# mainPower.net
KiCad netlist of a schematic drawn in Altium Designer
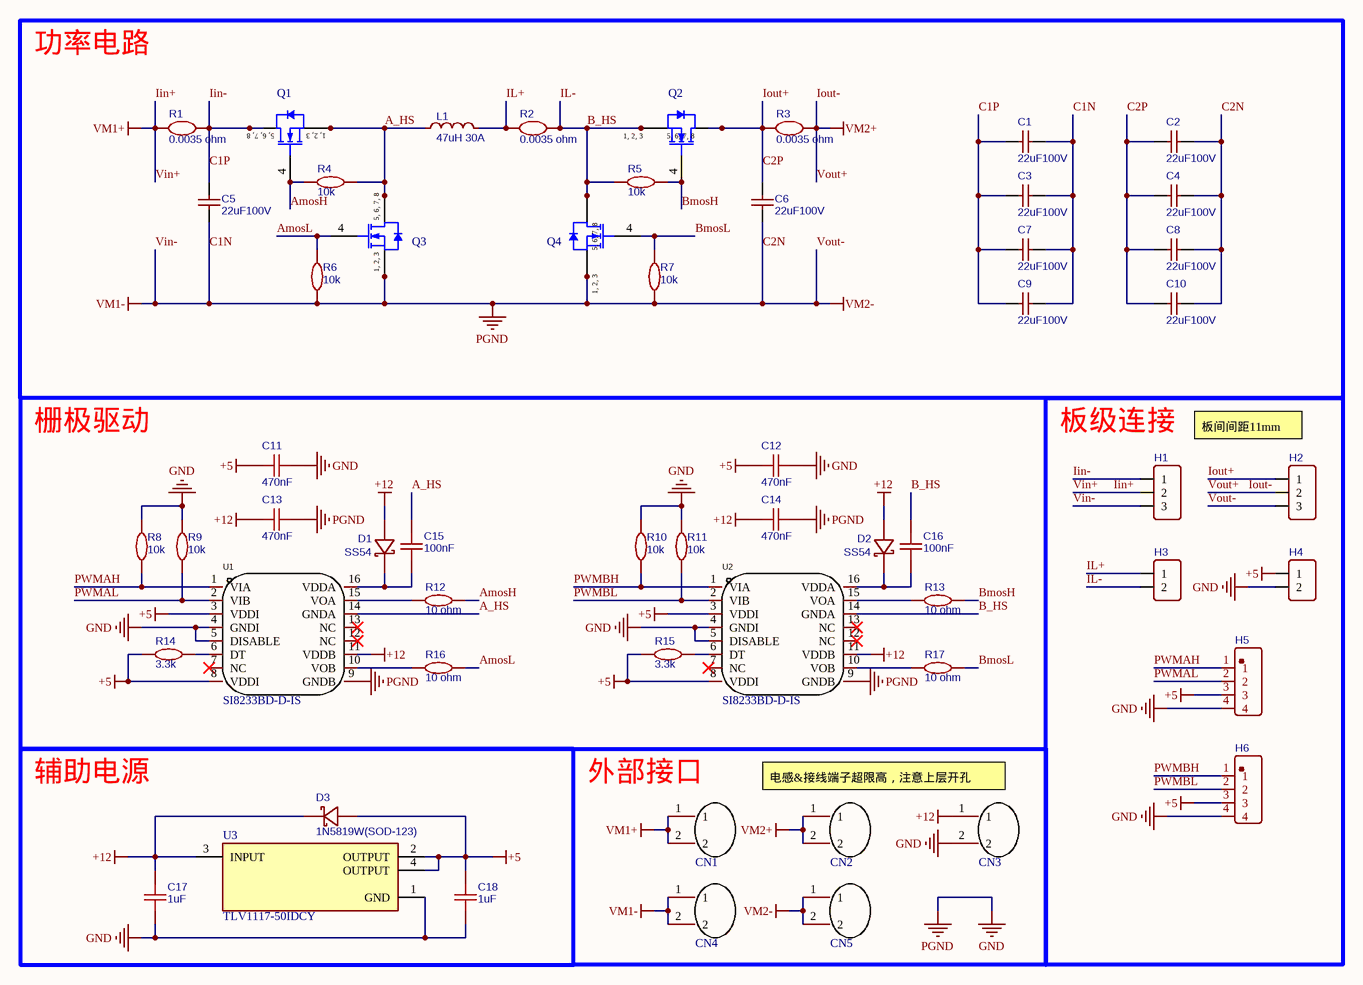
[diagram p0: mainPower.SchDoc]

(export (version "E")
  (design (tool "Eeschema 10.0.6"))
  (components
    (comp (ref "C1")
      (value "22uF100V")
      (footprint "C1206")
      (fields
        (field (name "BOM_MANUFACTURER PART") "1206B102K202NT")
        (field (name "BOM_SUPPLIER PART") "C9196")
      )
      (libsource (lib "RC_schlib") (part "C1206"))
    )
    (comp (ref "C2")
      (value "22uF100V")
      (footprint "C1206")
      (fields
        (field (name "BOM_MANUFACTURER PART") "1206B102K202NT")
        (field (name "BOM_SUPPLIER PART") "C9196")
      )
      (libsource (lib "RC_schlib") (part "C1206"))
    )
    (comp (ref "C3")
      (value "22uF100V")
      (footprint "C1206")
      (fields
        (field (name "BOM_MANUFACTURER PART") "1206B102K202NT")
        (field (name "BOM_SUPPLIER PART") "C9196")
      )
      (libsource (lib "RC_schlib") (part "C1206"))
    )
    (comp (ref "C4")
      (value "22uF100V")
      (footprint "C1206")
      (fields
        (field (name "BOM_MANUFACTURER PART") "1206B102K202NT")
        (field (name "BOM_SUPPLIER PART") "C9196")
      )
      (libsource (lib "RC_schlib") (part "C1206"))
    )
    (comp (ref "C5")
      (value "22uF100V")
      (footprint "C1206")
      (fields
        (field (name "BOM_MANUFACTURER PART") "1206B102K202NT")
        (field (name "BOM_SUPPLIER PART") "C9196")
      )
      (libsource (lib "RC_schlib") (part "C1206"))
    )
    (comp (ref "C6")
      (value "22uF100V")
      (footprint "C1206")
      (fields
        (field (name "BOM_MANUFACTURER PART") "1206B102K202NT")
        (field (name "BOM_SUPPLIER PART") "C9196")
      )
      (libsource (lib "RC_schlib") (part "C1206"))
    )
    (comp (ref "C7")
      (value "22uF100V")
      (footprint "C1206")
      (fields
        (field (name "BOM_MANUFACTURER PART") "1206B102K202NT")
        (field (name "BOM_SUPPLIER PART") "C9196")
      )
      (libsource (lib "RC_schlib") (part "C1206"))
    )
    (comp (ref "C8")
      (value "22uF100V")
      (footprint "C1206")
      (fields
        (field (name "BOM_MANUFACTURER PART") "1206B102K202NT")
        (field (name "BOM_SUPPLIER PART") "C9196")
      )
      (libsource (lib "RC_schlib") (part "C1206"))
    )
    (comp (ref "C9")
      (value "22uF100V")
      (footprint "C1206")
      (fields
        (field (name "BOM_MANUFACTURER PART") "1206B102K202NT")
        (field (name "BOM_SUPPLIER PART") "C9196")
      )
      (libsource (lib "RC_schlib") (part "C1206"))
    )
    (comp (ref "C10")
      (value "22uF100V")
      (footprint "C1206")
      (fields
        (field (name "BOM_MANUFACTURER PART") "1206B102K202NT")
        (field (name "BOM_SUPPLIER PART") "C9196")
      )
      (libsource (lib "RC_schlib") (part "C1206"))
    )
    (comp (ref "C11")
      (value "470nF")
      (footprint "C0603")
      (fields
        (field (name "BOM_MANUFACTURER PART") "CC0603KRX7R9BB104")
        (field (name "BOM_SUPPLIER PART") "C14663")
      )
      (libsource (lib "RC_schlib") (part "C0603"))
    )
    (comp (ref "C12")
      (value "470nF")
      (footprint "C0603")
      (fields
        (field (name "BOM_MANUFACTURER PART") "CC0603KRX7R9BB104")
        (field (name "BOM_SUPPLIER PART") "C14663")
      )
      (libsource (lib "RC_schlib") (part "C0603"))
    )
    (comp (ref "C13")
      (value "470nF")
      (footprint "C0603")
      (fields
        (field (name "BOM_MANUFACTURER PART") "CC0603KRX7R9BB104")
        (field (name "BOM_SUPPLIER PART") "C14663")
      )
      (libsource (lib "RC_schlib") (part "C0603"))
    )
    (comp (ref "C14")
      (value "470nF")
      (footprint "C0603")
      (fields
        (field (name "BOM_MANUFACTURER PART") "CC0603KRX7R9BB104")
        (field (name "BOM_SUPPLIER PART") "C14663")
      )
      (libsource (lib "RC_schlib") (part "C0603"))
    )
    (comp (ref "C15")
      (value "100nF")
      (footprint "C0603")
      (fields
        (field (name "BOM_MANUFACTURER PART") "CC0603KRX7R9BB104")
        (field (name "BOM_SUPPLIER PART") "C14663")
      )
      (libsource (lib "RC_schlib") (part "C0603"))
    )
    (comp (ref "C16")
      (value "100nF")
      (footprint "C0603")
      (fields
        (field (name "BOM_MANUFACTURER PART") "CC0603KRX7R9BB104")
        (field (name "BOM_SUPPLIER PART") "C14663")
      )
      (libsource (lib "RC_schlib") (part "C0603"))
    )
    (comp (ref "C17")
      (value "1uF")
      (footprint "C0603")
      (fields
        (field (name "BOM_MANUFACTURER PART") "CC0603KRX7R9BB104")
        (field (name "BOM_SUPPLIER PART") "C14663")
      )
      (libsource (lib "RC_schlib") (part "C0603"))
    )
    (comp (ref "C18")
      (value "1uF")
      (footprint "C0603")
      (fields
        (field (name "BOM_MANUFACTURER PART") "CC0603KRX7R9BB104")
        (field (name "BOM_SUPPLIER PART") "C14663")
      )
      (libsource (lib "RC_schlib") (part "C0603"))
    )
    (comp (ref "CN1")
      (value "1729128")
      (footprint "CONN-TH_2P-P5.08")
      (description "间距:5.08mm;排数:1;每排PIN数:2;安装方式:直针;额定电流:13.5A;额定电压:400V;工作温度范围:-;颜色:绿色;")
      (fields (field (name "MANUFACTURER") "Phoenix Contact(菲尼克斯)"))
      (libsource (lib "MKDSN") (part "MKDSN5.08-2P"))
    )
    (comp (ref "CN2")
      (value "1729128")
      (footprint "CONN-TH_2P-P5.08")
      (description "间距:5.08mm;排数:1;每排PIN数:2;安装方式:直针;额定电流:13.5A;额定电压:400V;工作温度范围:-;颜色:绿色;")
      (fields (field (name "MANUFACTURER") "Phoenix Contact(菲尼克斯)"))
      (libsource (lib "MKDSN") (part "MKDSN5.08-2P"))
    )
    (comp (ref "CN3")
      (value "1729128")
      (footprint "CONN-TH_2P-P5.08")
      (description "间距:5.08mm;排数:1;每排PIN数:2;安装方式:直针;额定电流:13.5A;额定电压:400V;工作温度范围:-;颜色:绿色;")
      (fields (field (name "MANUFACTURER") "Phoenix Contact(菲尼克斯)"))
      (libsource (lib "MKDSN") (part "MKDSN5.08-2P"))
    )
    (comp (ref "CN4")
      (value "1729128")
      (footprint "CONN-TH_2P-P5.08")
      (description "间距:5.08mm;排数:1;每排PIN数:2;安装方式:直针;额定电流:13.5A;额定电压:400V;工作温度范围:-;颜色:绿色;")
      (fields (field (name "MANUFACTURER") "Phoenix Contact(菲尼克斯)"))
      (libsource (lib "MKDSN") (part "MKDSN5.08-2P"))
    )
    (comp (ref "CN5")
      (value "1729128")
      (footprint "CONN-TH_2P-P5.08")
      (description "间距:5.08mm;排数:1;每排PIN数:2;安装方式:直针;额定电流:13.5A;额定电压:400V;工作温度范围:-;颜色:绿色;")
      (fields (field (name "MANUFACTURER") "Phoenix Contact(菲尼克斯)"))
      (libsource (lib "MKDSN") (part "MKDSN5.08-2P"))
    )
    (comp (ref "D1")
      (value "SS54")
      (footprint "SMA")
      (fields
        (field (name "BOM_SUPPLIER PART") "C2931787")
        (field (name "BOM_MANUFACTURER PART") "SS34")
        (field (name "CONTRIBUTOR") "LCSC")
      )
      (libsource (lib "Diode_schlib") (part "SS34(SMA)"))
    )
    (comp (ref "D2")
      (value "SS54")
      (footprint "SMA")
      (fields
        (field (name "BOM_SUPPLIER PART") "C2931787")
        (field (name "BOM_MANUFACTURER PART") "SS34")
        (field (name "CONTRIBUTOR") "LCSC")
      )
      (libsource (lib "Diode_schlib") (part "SS34(SMA)"))
    )
    (comp (ref "D3")
      (value "1N5819W(SOD-123)")
      (footprint "SOD-123")
      (fields
        (field (name "BOM_SUPPLIER PART") "C2931787")
        (field (name "BOM_MANUFACTURER PART") "SS34")
        (field (name "CONTRIBUTOR") "LCSC")
      )
      (libsource (lib "Diode_schlib") (part "1N5819W(SOD-123)"))
    )
    (comp (ref "H1")
      (value "Header-Male-2.54_1x3")
      (footprint "HDR2.54-LI-3P")
      (fields
        (field (name "BOM_MANUFACTURER PART") "Header2.54mm 1*3P")
        (field (name "BOM_SUPPLIER PART") "C49257")
      )
      (libsource (lib "2.54CN_schlib") (part "Header-Male-2.54_1x3"))
    )
    (comp (ref "H2")
      (value "Header-Male-2.54_1x3")
      (footprint "HDR2.54-LI-3P")
      (fields
        (field (name "BOM_MANUFACTURER PART") "Header2.54mm 1*3P")
        (field (name "BOM_SUPPLIER PART") "C49257")
      )
      (libsource (lib "2.54CN_schlib") (part "Header-Male-2.54_1x3"))
    )
    (comp (ref "H3")
      (value "Header-Male-2.54_1x2")
      (footprint "HDR2.54-LI-2P")
      (fields
        (field (name "BOM_MANUFACTURER PART") "Header2.54mm 1*3P")
        (field (name "BOM_SUPPLIER PART") "C49257")
      )
      (libsource (lib "2.54CN_schlib") (part "Header-Male-2.54_1x2"))
    )
    (comp (ref "H4")
      (value "Header-Male-2.54_1x2")
      (footprint "HDR2.54-LI-2P")
      (fields
        (field (name "BOM_MANUFACTURER PART") "Header2.54mm 1*3P")
        (field (name "BOM_SUPPLIER PART") "C49257")
      )
      (libsource (lib "2.54CN_schlib") (part "Header-Male-2.54_1x2"))
    )
    (comp (ref "H5")
      (value "Header-Male-2.54_1x4")
      (footprint "HDR2.54-LI-4P")
      (fields (field (name "BOM_SUPPLIER PART") "C247921") (field (name "CONTRIBUTOR") "LCSC"))
      (libsource (lib "2.54CN_schlib") (part "Header-Male-2.54_1x4"))
    )
    (comp (ref "H6")
      (value "Header-Male-2.54_1x4")
      (footprint "HDR2.54-LI-4P")
      (fields (field (name "BOM_SUPPLIER PART") "C247921") (field (name "CONTRIBUTOR") "LCSC"))
      (libsource (lib "2.54CN_schlib") (part "Header-Male-2.54_1x4"))
    )
    (comp (ref "L1")
      (value "47uH 30A")
      (footprint "106-125卧式")
      (fields
        (field (name "BOM_SUPPLIER PART") "C2936653")
        (field (name "BOM_MANUFACTURER PART") "HA42-4R7MT")
        (field (name "CONTRIBUTOR") "LCSC")
      )
      (libsource (lib "Inductance_schlib") (part "106-125铁硅铝磁环电感"))
    )
    (comp (ref "Q1")
      (value "BSC070N10NS3 G")
      (footprint "INF-PG-TDSON-8-1_V")
      (fields
        (field (name "MANUFACTURER") "Infineon")
        (field (name "MANUFACTURER PART NUMBER") "BSC070N10NS3G")
      )
      (libsource (lib "MOSFET_schlib") (part "BSC070N10NS3G"))
    )
    (comp (ref "Q2")
      (value "BSC070N10NS3 G")
      (footprint "INF-PG-TDSON-8-1_V")
      (fields
        (field (name "MANUFACTURER") "Infineon")
        (field (name "MANUFACTURER PART NUMBER") "BSC070N10NS3G")
      )
      (libsource (lib "MOSFET_schlib") (part "BSC070N10NS3G"))
    )
    (comp (ref "Q3")
      (value "BSC070N10NS3 G")
      (footprint "INF-PG-TDSON-8-1_V")
      (fields
        (field (name "MANUFACTURER") "Infineon")
        (field (name "MANUFACTURER PART NUMBER") "BSC070N10NS3G")
      )
      (libsource (lib "MOSFET_schlib") (part "BSC070N10NS3G"))
    )
    (comp (ref "Q4")
      (value "BSC070N10NS3 G")
      (footprint "INF-PG-TDSON-8-1_V")
      (fields
        (field (name "MANUFACTURER") "Infineon")
        (field (name "MANUFACTURER PART NUMBER") "BSC070N10NS3G")
      )
      (libsource (lib "MOSFET_schlib") (part "BSC070N10NS3G"))
    )
    (comp (ref "R1")
      (value "0.0035 ohm")
      (footprint "R2512")
      (fields
        (field (name "BOM_SUPPLIER PART") "C375694")
        (field (name "BOM_MANUFACTURER PART") "SR2512FK-0751RL")
        (field (name "CONTRIBUTOR") "LCSC")
      )
      (libsource (lib "RC_schlib") (part "R2512"))
    )
    (comp (ref "R2")
      (value "0.0035 ohm")
      (footprint "R2512")
      (fields
        (field (name "BOM_SUPPLIER PART") "C375694")
        (field (name "BOM_MANUFACTURER PART") "SR2512FK-0751RL")
        (field (name "CONTRIBUTOR") "LCSC")
      )
      (libsource (lib "RC_schlib") (part "R2512"))
    )
    (comp (ref "R3")
      (value "0.0035 ohm")
      (footprint "R2512")
      (fields
        (field (name "BOM_SUPPLIER PART") "C375694")
        (field (name "BOM_MANUFACTURER PART") "SR2512FK-0751RL")
        (field (name "CONTRIBUTOR") "LCSC")
      )
      (libsource (lib "RC_schlib") (part "R2512"))
    )
    (comp (ref "R4")
      (value "10k")
      (footprint "R0603")
      (fields
        (field (name "BOM_SUPPLIER PART") "C326890")
        (field (name "BOM_MANUFACTURER PART") "SR0603JR-071RL")
        (field (name "CONTRIBUTOR") "LCSC")
      )
      (libsource (lib "RC_schlib") (part "R0603"))
    )
    (comp (ref "R5")
      (value "10k")
      (footprint "R0603")
      (fields
        (field (name "BOM_SUPPLIER PART") "C326890")
        (field (name "BOM_MANUFACTURER PART") "SR0603JR-071RL")
        (field (name "CONTRIBUTOR") "LCSC")
      )
      (libsource (lib "RC_schlib") (part "R0603"))
    )
    (comp (ref "R6")
      (value "10k")
      (footprint "R0603")
      (fields
        (field (name "BOM_SUPPLIER PART") "C326890")
        (field (name "BOM_MANUFACTURER PART") "SR0603JR-071RL")
        (field (name "CONTRIBUTOR") "LCSC")
      )
      (libsource (lib "RC_schlib") (part "R0603"))
    )
    (comp (ref "R7")
      (value "10k")
      (footprint "R0603")
      (fields
        (field (name "BOM_SUPPLIER PART") "C326890")
        (field (name "BOM_MANUFACTURER PART") "SR0603JR-071RL")
        (field (name "CONTRIBUTOR") "LCSC")
      )
      (libsource (lib "RC_schlib") (part "R0603"))
    )
    (comp (ref "R8")
      (value "10k")
      (footprint "R0603")
      (fields
        (field (name "BOM_SUPPLIER PART") "C326890")
        (field (name "BOM_MANUFACTURER PART") "SR0603JR-071RL")
        (field (name "CONTRIBUTOR") "LCSC")
      )
      (libsource (lib "RC_schlib") (part "R0603"))
    )
    (comp (ref "R9")
      (value "10k")
      (footprint "R0603")
      (fields
        (field (name "BOM_SUPPLIER PART") "C326890")
        (field (name "BOM_MANUFACTURER PART") "SR0603JR-071RL")
        (field (name "CONTRIBUTOR") "LCSC")
      )
      (libsource (lib "RC_schlib") (part "R0603"))
    )
    (comp (ref "R10")
      (value "10k")
      (footprint "R0603")
      (fields
        (field (name "BOM_SUPPLIER PART") "C326890")
        (field (name "BOM_MANUFACTURER PART") "SR0603JR-071RL")
        (field (name "CONTRIBUTOR") "LCSC")
      )
      (libsource (lib "RC_schlib") (part "R0603"))
    )
    (comp (ref "R11")
      (value "10k")
      (footprint "R0603")
      (fields
        (field (name "BOM_SUPPLIER PART") "C326890")
        (field (name "BOM_MANUFACTURER PART") "SR0603JR-071RL")
        (field (name "CONTRIBUTOR") "LCSC")
      )
      (libsource (lib "RC_schlib") (part "R0603"))
    )
    (comp (ref "R12")
      (value "10 ohm")
      (footprint "R0603")
      (fields
        (field (name "BOM_SUPPLIER PART") "C326890")
        (field (name "BOM_MANUFACTURER PART") "SR0603JR-071RL")
        (field (name "CONTRIBUTOR") "LCSC")
      )
      (libsource (lib "RC_schlib") (part "R0603"))
    )
    (comp (ref "R13")
      (value "10 ohm")
      (footprint "R0603")
      (fields
        (field (name "BOM_SUPPLIER PART") "C326890")
        (field (name "BOM_MANUFACTURER PART") "SR0603JR-071RL")
        (field (name "CONTRIBUTOR") "LCSC")
      )
      (libsource (lib "RC_schlib") (part "R0603"))
    )
    (comp (ref "R14")
      (value "3.3k")
      (footprint "R0603")
      (fields
        (field (name "BOM_SUPPLIER PART") "C326890")
        (field (name "BOM_MANUFACTURER PART") "SR0603JR-071RL")
        (field (name "CONTRIBUTOR") "LCSC")
      )
      (libsource (lib "RC_schlib") (part "R0603"))
    )
    (comp (ref "R15")
      (value "3.3k")
      (footprint "R0603")
      (fields
        (field (name "BOM_SUPPLIER PART") "C326890")
        (field (name "BOM_MANUFACTURER PART") "SR0603JR-071RL")
        (field (name "CONTRIBUTOR") "LCSC")
      )
      (libsource (lib "RC_schlib") (part "R0603"))
    )
    (comp (ref "R16")
      (value "10 ohm")
      (footprint "R0603")
      (fields
        (field (name "BOM_SUPPLIER PART") "C326890")
        (field (name "BOM_MANUFACTURER PART") "SR0603JR-071RL")
        (field (name "CONTRIBUTOR") "LCSC")
      )
      (libsource (lib "RC_schlib") (part "R0603"))
    )
    (comp (ref "R17")
      (value "10 ohm")
      (footprint "R0603")
      (fields
        (field (name "BOM_SUPPLIER PART") "C326890")
        (field (name "BOM_MANUFACTURER PART") "SR0603JR-071RL")
        (field (name "CONTRIBUTOR") "LCSC")
      )
      (libsource (lib "RC_schlib") (part "R0603"))
    )
    (comp (ref "U1")
      (value "SI8233BD-D-IS")
      (footprint "SOIC-16_L10.3-W7.5-P1.27-LS10.3-BL")
      (description "高速隔离半桥栅极驱动器")
      (fields (field (name "MANUFACTURER") "SILICON LABS(芯科)"))
      (libsource (lib "IC_schlib") (part "SI8233BD-D-IS"))
    )
    (comp (ref "U2")
      (value "SI8233BD-D-IS")
      (footprint "SOIC-16_L10.3-W7.5-P1.27-LS10.3-BL")
      (description "高速隔离半桥栅极驱动器")
      (fields (field (name "MANUFACTURER") "SILICON LABS(芯科)"))
      (libsource (lib "IC_schlib") (part "SI8233BD-D-IS"))
    )
    (comp (ref "U3")
      (value "TLV1117-50IDCY")
      (footprint "FP-DCY0004A-MFG")
      (description "IC REG LINEAR 5V 800MA SOT223-4")
      (libsource (lib "Altium Content Vault") (part "e308c0431133a401381f8e374ae96fd"))
    )
  )
  (nets
    (net (code "1") (name "+5") (class "Default")
      (node (ref "C11") (pin "2") (pinfunction "2_2") (pintype "passive"))
      (node (ref "C12") (pin "2") (pinfunction "2_2") (pintype "passive"))
      (node (ref "C18") (pin "2") (pinfunction "2_2") (pintype "passive"))
      (node (ref "D3") (pin "1") (pinfunction "A_1") (pintype "passive"))
      (node (ref "H4") (pin "1") (pinfunction "1_1") (pintype "passive"))
      (node (ref "H5") (pin "3") (pinfunction "3_3") (pintype "passive"))
      (node (ref "H6") (pin "3") (pinfunction "3_3") (pintype "passive"))
      (node (ref "R14") (pin "1") (pinfunction "1_1") (pintype "passive"))
      (node (ref "R15") (pin "1") (pinfunction "1_1") (pintype "passive"))
      (node (ref "U1") (pin "3") (pinfunction "VDDI_3") (pintype "passive"))
      (node (ref "U1") (pin "8") (pinfunction "VDDI_8") (pintype "passive"))
      (node (ref "U2") (pin "3") (pinfunction "VDDI_3") (pintype "passive"))
      (node (ref "U2") (pin "8") (pinfunction "VDDI_8") (pintype "passive"))
      (node (ref "U3") (pin "2") (pinfunction "OUTPUT_2") (pintype "power_in"))
      (node (ref "U3") (pin "4") (pinfunction "OUTPUT_4") (pintype "power_in"))
    )
    (net (code "2") (name "+12") (class "Default")
      (node (ref "C13") (pin "2") (pinfunction "2_2") (pintype "passive"))
      (node (ref "C14") (pin "2") (pinfunction "2_2") (pintype "passive"))
      (node (ref "C17") (pin "2") (pinfunction "2_2") (pintype "passive"))
      (node (ref "CN3") (pin "1") (pinfunction "1_1") (pintype "passive"))
      (node (ref "D1") (pin "1") (pinfunction "A_1") (pintype "passive"))
      (node (ref "D2") (pin "1") (pinfunction "A_1") (pintype "passive"))
      (node (ref "D3") (pin "2") (pinfunction "K_2") (pintype "passive"))
      (node (ref "U1") (pin "11") (pinfunction "VDDB_11") (pintype "passive"))
      (node (ref "U2") (pin "11") (pinfunction "VDDB_11") (pintype "passive"))
      (node (ref "U3") (pin "3") (pinfunction "INPUT_3") (pintype "power_in"))
    )
    (net (code "3") (name "/A_HS") (class "Default")
      (node (ref "C15") (pin "2") (pinfunction "2_2") (pintype "passive"))
      (node (ref "L1") (pin "1") (pinfunction "1_1") (pintype "passive"))
      (node (ref "Q1") (pin "1") (pinfunction "SOURCE_1") (pintype "passive"))
      (node (ref "Q1") (pin "2") (pinfunction "SOURCE_2") (pintype "passive"))
      (node (ref "Q1") (pin "3") (pinfunction "SOURCE_3") (pintype "passive"))
      (node (ref "Q3") (pin "5") (pinfunction "DRAIN_5") (pintype "passive"))
      (node (ref "Q3") (pin "6") (pinfunction "DRAIN_6") (pintype "passive"))
      (node (ref "Q3") (pin "7") (pinfunction "DRAIN_7") (pintype "passive"))
      (node (ref "Q3") (pin "8") (pinfunction "DRAIN_8") (pintype "passive"))
      (node (ref "R4") (pin "1") (pinfunction "1_1") (pintype "passive"))
      (node (ref "U1") (pin "14") (pinfunction "GNDA_14") (pintype "passive"))
    )
    (net (code "4") (name "/AmosH") (class "Default")
      (node (ref "Q1") (pin "4") (pinfunction "GATE_4") (pintype "passive"))
      (node (ref "R12") (pin "2") (pinfunction "2_2") (pintype "passive"))
      (node (ref "R4") (pin "2") (pinfunction "2_2") (pintype "passive"))
    )
    (net (code "5") (name "/AmosL") (class "Default")
      (node (ref "Q3") (pin "4") (pinfunction "GATE_4") (pintype "passive"))
      (node (ref "R16") (pin "2") (pinfunction "2_2") (pintype "passive"))
      (node (ref "R6") (pin "2") (pinfunction "2_2") (pintype "passive"))
    )
    (net (code "6") (name "/B_HS") (class "Default")
      (node (ref "C16") (pin "2") (pinfunction "2_2") (pintype "passive"))
      (node (ref "H3") (pin "2") (pinfunction "2_2") (pintype "passive"))
      (node (ref "Q2") (pin "1") (pinfunction "SOURCE_1") (pintype "passive"))
      (node (ref "Q2") (pin "2") (pinfunction "SOURCE_2") (pintype "passive"))
      (node (ref "Q2") (pin "3") (pinfunction "SOURCE_3") (pintype "passive"))
      (node (ref "Q4") (pin "5") (pinfunction "DRAIN_5") (pintype "passive"))
      (node (ref "Q4") (pin "6") (pinfunction "DRAIN_6") (pintype "passive"))
      (node (ref "Q4") (pin "7") (pinfunction "DRAIN_7") (pintype "passive"))
      (node (ref "Q4") (pin "8") (pinfunction "DRAIN_8") (pintype "passive"))
      (node (ref "R2") (pin "2") (pinfunction "2_2") (pintype "passive"))
      (node (ref "R5") (pin "2") (pinfunction "2_2") (pintype "passive"))
      (node (ref "U2") (pin "14") (pinfunction "GNDA_14") (pintype "passive"))
    )
    (net (code "7") (name "/BmosH") (class "Default")
      (node (ref "Q2") (pin "4") (pinfunction "GATE_4") (pintype "passive"))
      (node (ref "R13") (pin "2") (pinfunction "2_2") (pintype "passive"))
      (node (ref "R5") (pin "1") (pinfunction "1_1") (pintype "passive"))
    )
    (net (code "8") (name "/BmosL") (class "Default")
      (node (ref "Q4") (pin "4") (pinfunction "GATE_4") (pintype "passive"))
      (node (ref "R17") (pin "2") (pinfunction "2_2") (pintype "passive"))
      (node (ref "R7") (pin "2") (pinfunction "2_2") (pintype "passive"))
    )
    (net (code "9") (name "/C1P") (class "Default")
      (node (ref "C1") (pin "1") (pinfunction "1_1") (pintype "passive"))
      (node (ref "C3") (pin "1") (pinfunction "1_1") (pintype "passive"))
      (node (ref "C5") (pin "2") (pinfunction "2_2") (pintype "passive"))
      (node (ref "C7") (pin "1") (pinfunction "1_1") (pintype "passive"))
      (node (ref "C9") (pin "1") (pinfunction "1_1") (pintype "passive"))
      (node (ref "H1") (pin "1") (pinfunction "1_1") (pintype "passive"))
      (node (ref "Q1") (pin "5") (pinfunction "DRAIN_5") (pintype "passive"))
      (node (ref "Q1") (pin "6") (pinfunction "DRAIN_6") (pintype "passive"))
      (node (ref "Q1") (pin "7") (pinfunction "DRAIN_7") (pintype "passive"))
      (node (ref "Q1") (pin "8") (pinfunction "DRAIN_8") (pintype "passive"))
      (node (ref "R1") (pin "2") (pinfunction "2_2") (pintype "passive"))
    )
    (net (code "10") (name "/C2P") (class "Default")
      (node (ref "C10") (pin "1") (pinfunction "1_1") (pintype "passive"))
      (node (ref "C2") (pin "1") (pinfunction "1_1") (pintype "passive"))
      (node (ref "C4") (pin "1") (pinfunction "1_1") (pintype "passive"))
      (node (ref "C6") (pin "2") (pinfunction "2_2") (pintype "passive"))
      (node (ref "C8") (pin "1") (pinfunction "1_1") (pintype "passive"))
      (node (ref "H2") (pin "1") (pinfunction "1_1") (pintype "passive"))
      (node (ref "Q2") (pin "5") (pinfunction "DRAIN_5") (pintype "passive"))
      (node (ref "Q2") (pin "6") (pinfunction "DRAIN_6") (pintype "passive"))
      (node (ref "Q2") (pin "7") (pinfunction "DRAIN_7") (pintype "passive"))
      (node (ref "Q2") (pin "8") (pinfunction "DRAIN_8") (pintype "passive"))
      (node (ref "R3") (pin "1") (pinfunction "1_1") (pintype "passive"))
    )
    (net (code "11") (name "/IL+") (class "Default")
      (node (ref "H3") (pin "1") (pinfunction "1_1") (pintype "passive"))
      (node (ref "L1") (pin "2") (pinfunction "2_2") (pintype "passive"))
      (node (ref "R2") (pin "1") (pinfunction "1_1") (pintype "passive"))
    )
    (net (code "12") (name "/PWMAH") (class "Default")
      (node (ref "H5") (pin "1") (pinfunction "1_1") (pintype "passive"))
      (node (ref "R8") (pin "1") (pinfunction "1_1") (pintype "passive"))
      (node (ref "U1") (pin "1") (pinfunction "VIA_1") (pintype "passive"))
    )
    (net (code "13") (name "/PWMAL") (class "Default")
      (node (ref "H5") (pin "2") (pinfunction "2_2") (pintype "passive"))
      (node (ref "R9") (pin "1") (pinfunction "1_1") (pintype "passive"))
      (node (ref "U1") (pin "2") (pinfunction "VIB_2") (pintype "passive"))
    )
    (net (code "14") (name "/PWMBH") (class "Default")
      (node (ref "H6") (pin "1") (pinfunction "1_1") (pintype "passive"))
      (node (ref "R10") (pin "1") (pinfunction "1_1") (pintype "passive"))
      (node (ref "U2") (pin "1") (pinfunction "VIA_1") (pintype "passive"))
    )
    (net (code "15") (name "/PWMBL") (class "Default")
      (node (ref "H6") (pin "2") (pinfunction "2_2") (pintype "passive"))
      (node (ref "R11") (pin "1") (pinfunction "1_1") (pintype "passive"))
      (node (ref "U2") (pin "2") (pinfunction "VIB_2") (pintype "passive"))
    )
    (net (code "16") (name "GND") (class "Default")
      (node (ref "C1") (pin "2") (pinfunction "2_2") (pintype "passive"))
      (node (ref "C10") (pin "2") (pinfunction "2_2") (pintype "passive"))
      (node (ref "C11") (pin "1") (pinfunction "1_1") (pintype "passive"))
      (node (ref "C12") (pin "1") (pinfunction "1_1") (pintype "passive"))
      (node (ref "C13") (pin "1") (pinfunction "1_1") (pintype "passive"))
      (node (ref "C14") (pin "1") (pinfunction "1_1") (pintype "passive"))
      (node (ref "C17") (pin "1") (pinfunction "1_1") (pintype "passive"))
      (node (ref "C18") (pin "1") (pinfunction "1_1") (pintype "passive"))
      (node (ref "C2") (pin "2") (pinfunction "2_2") (pintype "passive"))
      (node (ref "C3") (pin "2") (pinfunction "2_2") (pintype "passive"))
      (node (ref "C4") (pin "2") (pinfunction "2_2") (pintype "passive"))
      (node (ref "C5") (pin "1") (pinfunction "1_1") (pintype "passive"))
      (node (ref "C6") (pin "1") (pinfunction "1_1") (pintype "passive"))
      (node (ref "C7") (pin "2") (pinfunction "2_2") (pintype "passive"))
      (node (ref "C8") (pin "2") (pinfunction "2_2") (pintype "passive"))
      (node (ref "C9") (pin "2") (pinfunction "2_2") (pintype "passive"))
      (node (ref "CN3") (pin "2") (pinfunction "2_2") (pintype "passive"))
      (node (ref "CN4") (pin "1") (pinfunction "1_1") (pintype "passive"))
      (node (ref "CN4") (pin "2") (pinfunction "2_2") (pintype "passive"))
      (node (ref "CN5") (pin "1") (pinfunction "1_1") (pintype "passive"))
      (node (ref "CN5") (pin "2") (pinfunction "2_2") (pintype "passive"))
      (node (ref "H1") (pin "3") (pinfunction "3_3") (pintype "passive"))
      (node (ref "H2") (pin "3") (pinfunction "3_3") (pintype "passive"))
      (node (ref "H4") (pin "2") (pinfunction "2_2") (pintype "passive"))
      (node (ref "H5") (pin "4") (pinfunction "4_4") (pintype "passive"))
      (node (ref "H6") (pin "4") (pinfunction "4_4") (pintype "passive"))
      (node (ref "Q3") (pin "1") (pinfunction "SOURCE_1") (pintype "passive"))
      (node (ref "Q3") (pin "2") (pinfunction "SOURCE_2") (pintype "passive"))
      (node (ref "Q3") (pin "3") (pinfunction "SOURCE_3") (pintype "passive"))
      (node (ref "Q4") (pin "1") (pinfunction "SOURCE_1") (pintype "passive"))
      (node (ref "Q4") (pin "2") (pinfunction "SOURCE_2") (pintype "passive"))
      (node (ref "Q4") (pin "3") (pinfunction "SOURCE_3") (pintype "passive"))
      (node (ref "R10") (pin "2") (pinfunction "2_2") (pintype "passive"))
      (node (ref "R11") (pin "2") (pinfunction "2_2") (pintype "passive"))
      (node (ref "R6") (pin "1") (pinfunction "1_1") (pintype "passive"))
      (node (ref "R7") (pin "1") (pinfunction "1_1") (pintype "passive"))
      (node (ref "R8") (pin "2") (pinfunction "2_2") (pintype "passive"))
      (node (ref "R9") (pin "2") (pinfunction "2_2") (pintype "passive"))
      (node (ref "U1") (pin "4") (pinfunction "GNDI_4") (pintype "passive"))
      (node (ref "U1") (pin "5") (pinfunction "DISABLE_5") (pintype "passive"))
      (node (ref "U1") (pin "9") (pinfunction "GNDB_9") (pintype "passive"))
      (node (ref "U2") (pin "4") (pinfunction "GNDI_4") (pintype "passive"))
      (node (ref "U2") (pin "5") (pinfunction "DISABLE_5") (pintype "passive"))
      (node (ref "U2") (pin "9") (pinfunction "GNDB_9") (pintype "passive"))
      (node (ref "U3") (pin "1") (pinfunction "GND_1") (pintype "power_in"))
    )
    (net (code "17") (name "Net-(D1-K)") (class "Default")
      (node (ref "C15") (pin "1") (pinfunction "1_1") (pintype "passive"))
      (node (ref "D1") (pin "2") (pinfunction "K_2") (pintype "passive"))
      (node (ref "U1") (pin "16") (pinfunction "VDDA_16") (pintype "passive"))
    )
    (net (code "18") (name "Net-(D2-K)") (class "Default")
      (node (ref "C16") (pin "1") (pinfunction "1_1") (pintype "passive"))
      (node (ref "D2") (pin "2") (pinfunction "K_2") (pintype "passive"))
      (node (ref "U2") (pin "16") (pinfunction "VDDA_16") (pintype "passive"))
    )
    (net (code "19") (name "Net-(U1-DT)") (class "Default")
      (node (ref "R14") (pin "2") (pinfunction "2_2") (pintype "passive"))
      (node (ref "U1") (pin "6") (pinfunction "DT_6") (pintype "passive"))
    )
    (net (code "20") (name "Net-(U1-VOA)") (class "Default")
      (node (ref "R12") (pin "1") (pinfunction "1_1") (pintype "passive"))
      (node (ref "U1") (pin "15") (pinfunction "VOA_15") (pintype "passive"))
    )
    (net (code "21") (name "Net-(U1-VOB)") (class "Default")
      (node (ref "R16") (pin "1") (pinfunction "1_1") (pintype "passive"))
      (node (ref "U1") (pin "10") (pinfunction "VOB_10") (pintype "passive"))
    )
    (net (code "22") (name "Net-(U2-DT)") (class "Default")
      (node (ref "R15") (pin "2") (pinfunction "2_2") (pintype "passive"))
      (node (ref "U2") (pin "6") (pinfunction "DT_6") (pintype "passive"))
    )
    (net (code "23") (name "Net-(U2-VOA)") (class "Default")
      (node (ref "R13") (pin "1") (pinfunction "1_1") (pintype "passive"))
      (node (ref "U2") (pin "15") (pinfunction "VOA_15") (pintype "passive"))
    )
    (net (code "24") (name "Net-(U2-VOB)") (class "Default")
      (node (ref "R17") (pin "1") (pinfunction "1_1") (pintype "passive"))
      (node (ref "U2") (pin "10") (pinfunction "VOB_10") (pintype "passive"))
    )
    (net (code "25") (name "VM1+") (class "Default")
      (node (ref "CN1") (pin "1") (pinfunction "1_1") (pintype "passive"))
      (node (ref "CN1") (pin "2") (pinfunction "2_2") (pintype "passive"))
      (node (ref "H1") (pin "2") (pinfunction "2_2") (pintype "passive"))
      (node (ref "R1") (pin "1") (pinfunction "1_1") (pintype "passive"))
    )
    (net (code "26") (name "VM2+") (class "Default")
      (node (ref "CN2") (pin "1") (pinfunction "1_1") (pintype "passive"))
      (node (ref "CN2") (pin "2") (pinfunction "2_2") (pintype "passive"))
      (node (ref "H2") (pin "2") (pinfunction "2_2") (pintype "passive"))
      (node (ref "R3") (pin "2") (pinfunction "2_2") (pintype "passive"))
    )
    (net (code "27") (name "unconnected-(U1-NC-Pad7)") (class "Default")
      (node (ref "U1") (pin "7") (pinfunction "NC_7") (pintype "passive+no_connect"))
    )
    (net (code "28") (name "unconnected-(U1-NC-Pad12)") (class "Default")
      (node (ref "U1") (pin "12") (pinfunction "NC_12") (pintype "passive+no_connect"))
    )
    (net (code "29") (name "unconnected-(U1-NC-Pad13)") (class "Default")
      (node (ref "U1") (pin "13") (pinfunction "NC_13") (pintype "passive+no_connect"))
    )
    (net (code "30") (name "unconnected-(U2-NC-Pad7)") (class "Default")
      (node (ref "U2") (pin "7") (pinfunction "NC_7") (pintype "passive+no_connect"))
    )
    (net (code "31") (name "unconnected-(U2-NC-Pad12)") (class "Default")
      (node (ref "U2") (pin "12") (pinfunction "NC_12") (pintype "passive+no_connect"))
    )
    (net (code "32") (name "unconnected-(U2-NC-Pad13)") (class "Default")
      (node (ref "U2") (pin "13") (pinfunction "NC_13") (pintype "passive+no_connect"))
    )
  )
)
